# GPIO.net
KiCad netlist of a schematic drawn in EAGLE
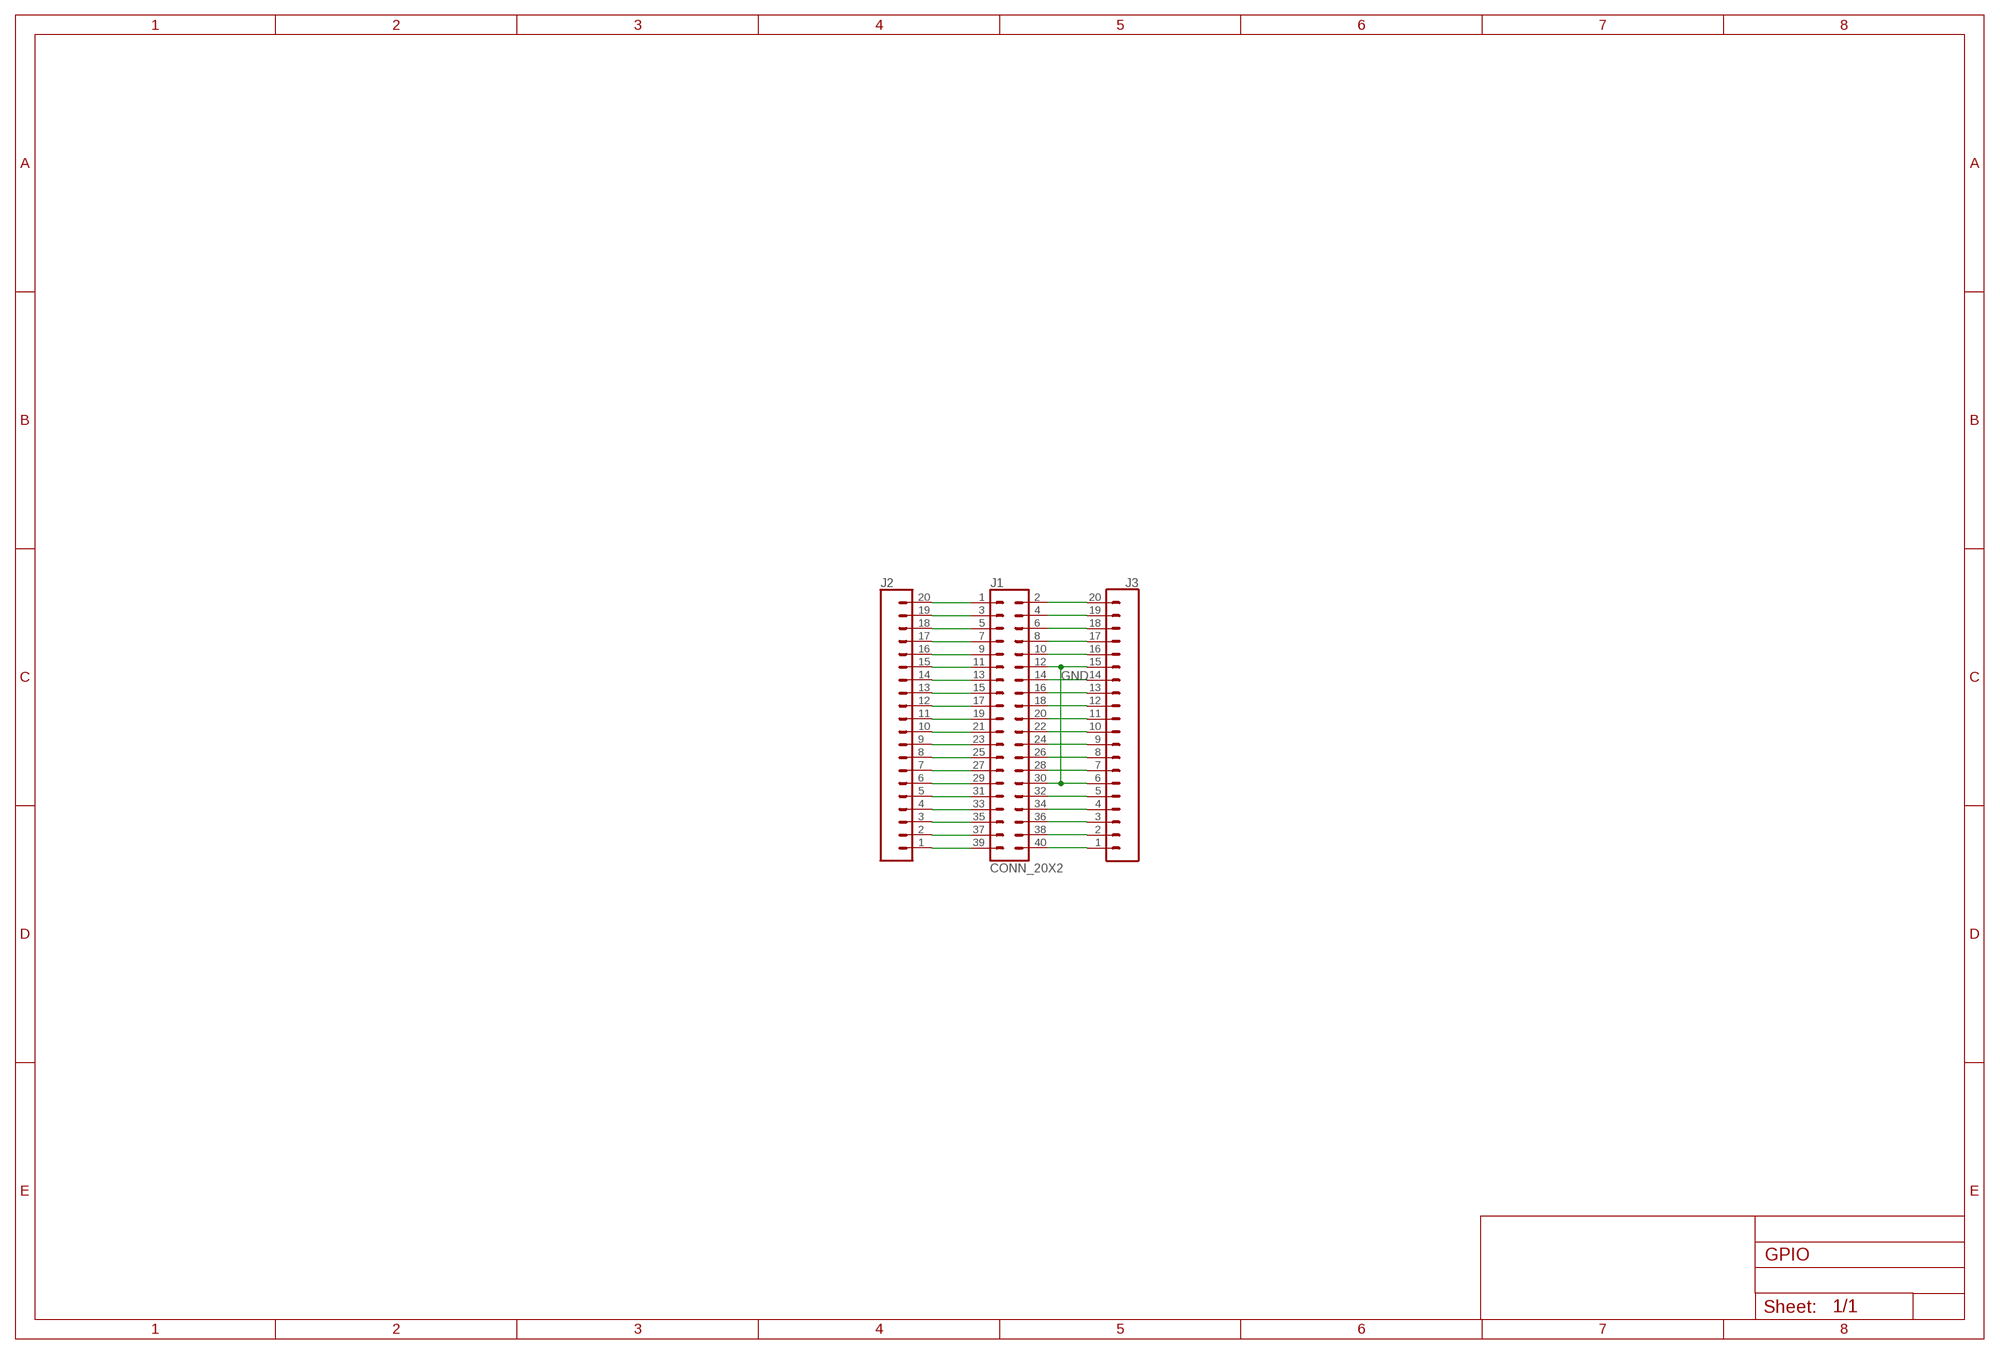
[diagram p0: schematic, sheet 1]

(export (version "E")
  (design (tool "Eeschema 10.0.6"))
  (components
    (comp (ref "J1")
      (value "CONN_20X2")
      (footprint "eagle-import:2X20")
      (libsource (lib "eagle-import") (part "CONN_20X2"))
    )
    (comp (ref "J2")
      (value "CONN_20")
      (footprint "eagle-import:1X20")
      (libsource (lib "eagle-import") (part "CONN_20"))
    )
    (comp (ref "J3")
      (value "CONN_20")
      (footprint "eagle-import:1X20")
      (libsource (lib "eagle-import") (part "CONN_20"))
    )
  )
  (nets
    (net (code "1") (name "/GND") (class "Default")
      (node (ref "J1") (pin "12") (pinfunction "12_12") (pintype "passive"))
      (node (ref "J1") (pin "30") (pinfunction "30_30") (pintype "passive"))
      (node (ref "J3") (pin "15") (pinfunction "15_15") (pintype "passive"))
      (node (ref "J3") (pin "6") (pinfunction "6_6") (pintype "passive"))
    )
    (net (code "2") (name "Net-(J1-Pad1)") (class "Default")
      (node (ref "J1") (pin "1") (pinfunction "1_1") (pintype "passive"))
      (node (ref "J2") (pin "20") (pinfunction "20_20") (pintype "passive"))
    )
    (net (code "3") (name "Net-(J1-Pad2)") (class "Default")
      (node (ref "J1") (pin "2") (pinfunction "2_2") (pintype "passive"))
      (node (ref "J3") (pin "20") (pinfunction "20_20") (pintype "passive"))
    )
    (net (code "4") (name "Net-(J1-Pad3)") (class "Default")
      (node (ref "J1") (pin "3") (pinfunction "3_3") (pintype "passive"))
      (node (ref "J2") (pin "19") (pinfunction "19_19") (pintype "passive"))
    )
    (net (code "5") (name "Net-(J1-Pad4)") (class "Default")
      (node (ref "J1") (pin "4") (pinfunction "4_4") (pintype "passive"))
      (node (ref "J3") (pin "19") (pinfunction "19_19") (pintype "passive"))
    )
    (net (code "6") (name "Net-(J1-Pad5)") (class "Default")
      (node (ref "J1") (pin "5") (pinfunction "5_5") (pintype "passive"))
      (node (ref "J2") (pin "18") (pinfunction "18_18") (pintype "passive"))
    )
    (net (code "7") (name "Net-(J1-Pad6)") (class "Default")
      (node (ref "J1") (pin "6") (pinfunction "6_6") (pintype "passive"))
      (node (ref "J3") (pin "18") (pinfunction "18_18") (pintype "passive"))
    )
    (net (code "8") (name "Net-(J1-Pad7)") (class "Default")
      (node (ref "J1") (pin "7") (pinfunction "7_7") (pintype "passive"))
      (node (ref "J2") (pin "17") (pinfunction "17_17") (pintype "passive"))
    )
    (net (code "9") (name "Net-(J1-Pad8)") (class "Default")
      (node (ref "J1") (pin "8") (pinfunction "8_8") (pintype "passive"))
      (node (ref "J3") (pin "17") (pinfunction "17_17") (pintype "passive"))
    )
    (net (code "10") (name "Net-(J1-Pad9)") (class "Default")
      (node (ref "J1") (pin "9") (pinfunction "9_9") (pintype "passive"))
      (node (ref "J2") (pin "16") (pinfunction "16_16") (pintype "passive"))
    )
    (net (code "11") (name "Net-(J1-Pad10)") (class "Default")
      (node (ref "J1") (pin "10") (pinfunction "10_10") (pintype "passive"))
      (node (ref "J3") (pin "16") (pinfunction "16_16") (pintype "passive"))
    )
    (net (code "12") (name "Net-(J1-Pad11)") (class "Default")
      (node (ref "J1") (pin "11") (pinfunction "11_11") (pintype "passive"))
      (node (ref "J2") (pin "15") (pinfunction "15_15") (pintype "passive"))
    )
    (net (code "13") (name "Net-(J1-Pad13)") (class "Default")
      (node (ref "J1") (pin "13") (pinfunction "13_13") (pintype "passive"))
      (node (ref "J2") (pin "14") (pinfunction "14_14") (pintype "passive"))
    )
    (net (code "14") (name "Net-(J1-Pad14)") (class "Default")
      (node (ref "J1") (pin "14") (pinfunction "14_14") (pintype "passive"))
      (node (ref "J3") (pin "14") (pinfunction "14_14") (pintype "passive"))
    )
    (net (code "15") (name "Net-(J1-Pad15)") (class "Default")
      (node (ref "J1") (pin "15") (pinfunction "15_15") (pintype "passive"))
      (node (ref "J2") (pin "13") (pinfunction "13_13") (pintype "passive"))
    )
    (net (code "16") (name "Net-(J1-Pad16)") (class "Default")
      (node (ref "J1") (pin "16") (pinfunction "16_16") (pintype "passive"))
      (node (ref "J3") (pin "13") (pinfunction "13_13") (pintype "passive"))
    )
    (net (code "17") (name "Net-(J1-Pad17)") (class "Default")
      (node (ref "J1") (pin "17") (pinfunction "17_17") (pintype "passive"))
      (node (ref "J2") (pin "12") (pinfunction "12_12") (pintype "passive"))
    )
    (net (code "18") (name "Net-(J1-Pad18)") (class "Default")
      (node (ref "J1") (pin "18") (pinfunction "18_18") (pintype "passive"))
      (node (ref "J3") (pin "12") (pinfunction "12_12") (pintype "passive"))
    )
    (net (code "19") (name "Net-(J1-Pad19)") (class "Default")
      (node (ref "J1") (pin "19") (pinfunction "19_19") (pintype "passive"))
      (node (ref "J2") (pin "11") (pinfunction "11_11") (pintype "passive"))
    )
    (net (code "20") (name "Net-(J1-Pad20)") (class "Default")
      (node (ref "J1") (pin "20") (pinfunction "20_20") (pintype "passive"))
      (node (ref "J3") (pin "11") (pinfunction "11_11") (pintype "passive"))
    )
    (net (code "21") (name "Net-(J1-Pad21)") (class "Default")
      (node (ref "J1") (pin "21") (pinfunction "21_21") (pintype "passive"))
      (node (ref "J2") (pin "10") (pinfunction "10_10") (pintype "passive"))
    )
    (net (code "22") (name "Net-(J1-Pad22)") (class "Default")
      (node (ref "J1") (pin "22") (pinfunction "22_22") (pintype "passive"))
      (node (ref "J3") (pin "10") (pinfunction "10_10") (pintype "passive"))
    )
    (net (code "23") (name "Net-(J1-Pad23)") (class "Default")
      (node (ref "J1") (pin "23") (pinfunction "23_23") (pintype "passive"))
      (node (ref "J2") (pin "9") (pinfunction "9_9") (pintype "passive"))
    )
    (net (code "24") (name "Net-(J1-Pad24)") (class "Default")
      (node (ref "J1") (pin "24") (pinfunction "24_24") (pintype "passive"))
      (node (ref "J3") (pin "9") (pinfunction "9_9") (pintype "passive"))
    )
    (net (code "25") (name "Net-(J1-Pad25)") (class "Default")
      (node (ref "J1") (pin "25") (pinfunction "25_25") (pintype "passive"))
      (node (ref "J2") (pin "8") (pinfunction "8_8") (pintype "passive"))
    )
    (net (code "26") (name "Net-(J1-Pad26)") (class "Default")
      (node (ref "J1") (pin "26") (pinfunction "26_26") (pintype "passive"))
      (node (ref "J3") (pin "8") (pinfunction "8_8") (pintype "passive"))
    )
    (net (code "27") (name "Net-(J1-Pad27)") (class "Default")
      (node (ref "J1") (pin "27") (pinfunction "27_27") (pintype "passive"))
      (node (ref "J2") (pin "7") (pinfunction "7_7") (pintype "passive"))
    )
    (net (code "28") (name "Net-(J1-Pad28)") (class "Default")
      (node (ref "J1") (pin "28") (pinfunction "28_28") (pintype "passive"))
      (node (ref "J3") (pin "7") (pinfunction "7_7") (pintype "passive"))
    )
    (net (code "29") (name "Net-(J1-Pad29)") (class "Default")
      (node (ref "J1") (pin "29") (pinfunction "29_29") (pintype "passive"))
      (node (ref "J2") (pin "6") (pinfunction "6_6") (pintype "passive"))
    )
    (net (code "30") (name "Net-(J1-Pad31)") (class "Default")
      (node (ref "J1") (pin "31") (pinfunction "31_31") (pintype "passive"))
      (node (ref "J2") (pin "5") (pinfunction "5_5") (pintype "passive"))
    )
    (net (code "31") (name "Net-(J1-Pad32)") (class "Default")
      (node (ref "J1") (pin "32") (pinfunction "32_32") (pintype "passive"))
      (node (ref "J3") (pin "5") (pinfunction "5_5") (pintype "passive"))
    )
    (net (code "32") (name "Net-(J1-Pad33)") (class "Default")
      (node (ref "J1") (pin "33") (pinfunction "33_33") (pintype "passive"))
      (node (ref "J2") (pin "4") (pinfunction "4_4") (pintype "passive"))
    )
    (net (code "33") (name "Net-(J1-Pad34)") (class "Default")
      (node (ref "J1") (pin "34") (pinfunction "34_34") (pintype "passive"))
      (node (ref "J3") (pin "4") (pinfunction "4_4") (pintype "passive"))
    )
    (net (code "34") (name "Net-(J1-Pad35)") (class "Default")
      (node (ref "J1") (pin "35") (pinfunction "35_35") (pintype "passive"))
      (node (ref "J2") (pin "3") (pinfunction "3_3") (pintype "passive"))
    )
    (net (code "35") (name "Net-(J1-Pad36)") (class "Default")
      (node (ref "J1") (pin "36") (pinfunction "36_36") (pintype "passive"))
      (node (ref "J3") (pin "3") (pinfunction "3_3") (pintype "passive"))
    )
    (net (code "36") (name "Net-(J1-Pad37)") (class "Default")
      (node (ref "J1") (pin "37") (pinfunction "37_37") (pintype "passive"))
      (node (ref "J2") (pin "2") (pinfunction "2_2") (pintype "passive"))
    )
    (net (code "37") (name "Net-(J1-Pad38)") (class "Default")
      (node (ref "J1") (pin "38") (pinfunction "38_38") (pintype "passive"))
      (node (ref "J3") (pin "2") (pinfunction "2_2") (pintype "passive"))
    )
    (net (code "38") (name "Net-(J1-Pad39)") (class "Default")
      (node (ref "J1") (pin "39") (pinfunction "39_39") (pintype "passive"))
      (node (ref "J2") (pin "1") (pinfunction "1_1") (pintype "passive"))
    )
    (net (code "39") (name "Net-(J1-Pad40)") (class "Default")
      (node (ref "J1") (pin "40") (pinfunction "40_40") (pintype "passive"))
      (node (ref "J3") (pin "1") (pinfunction "1_1") (pintype "passive"))
    )
  )
)
